# PLL.net
KiCad netlist of a schematic drawn in Altium Designer
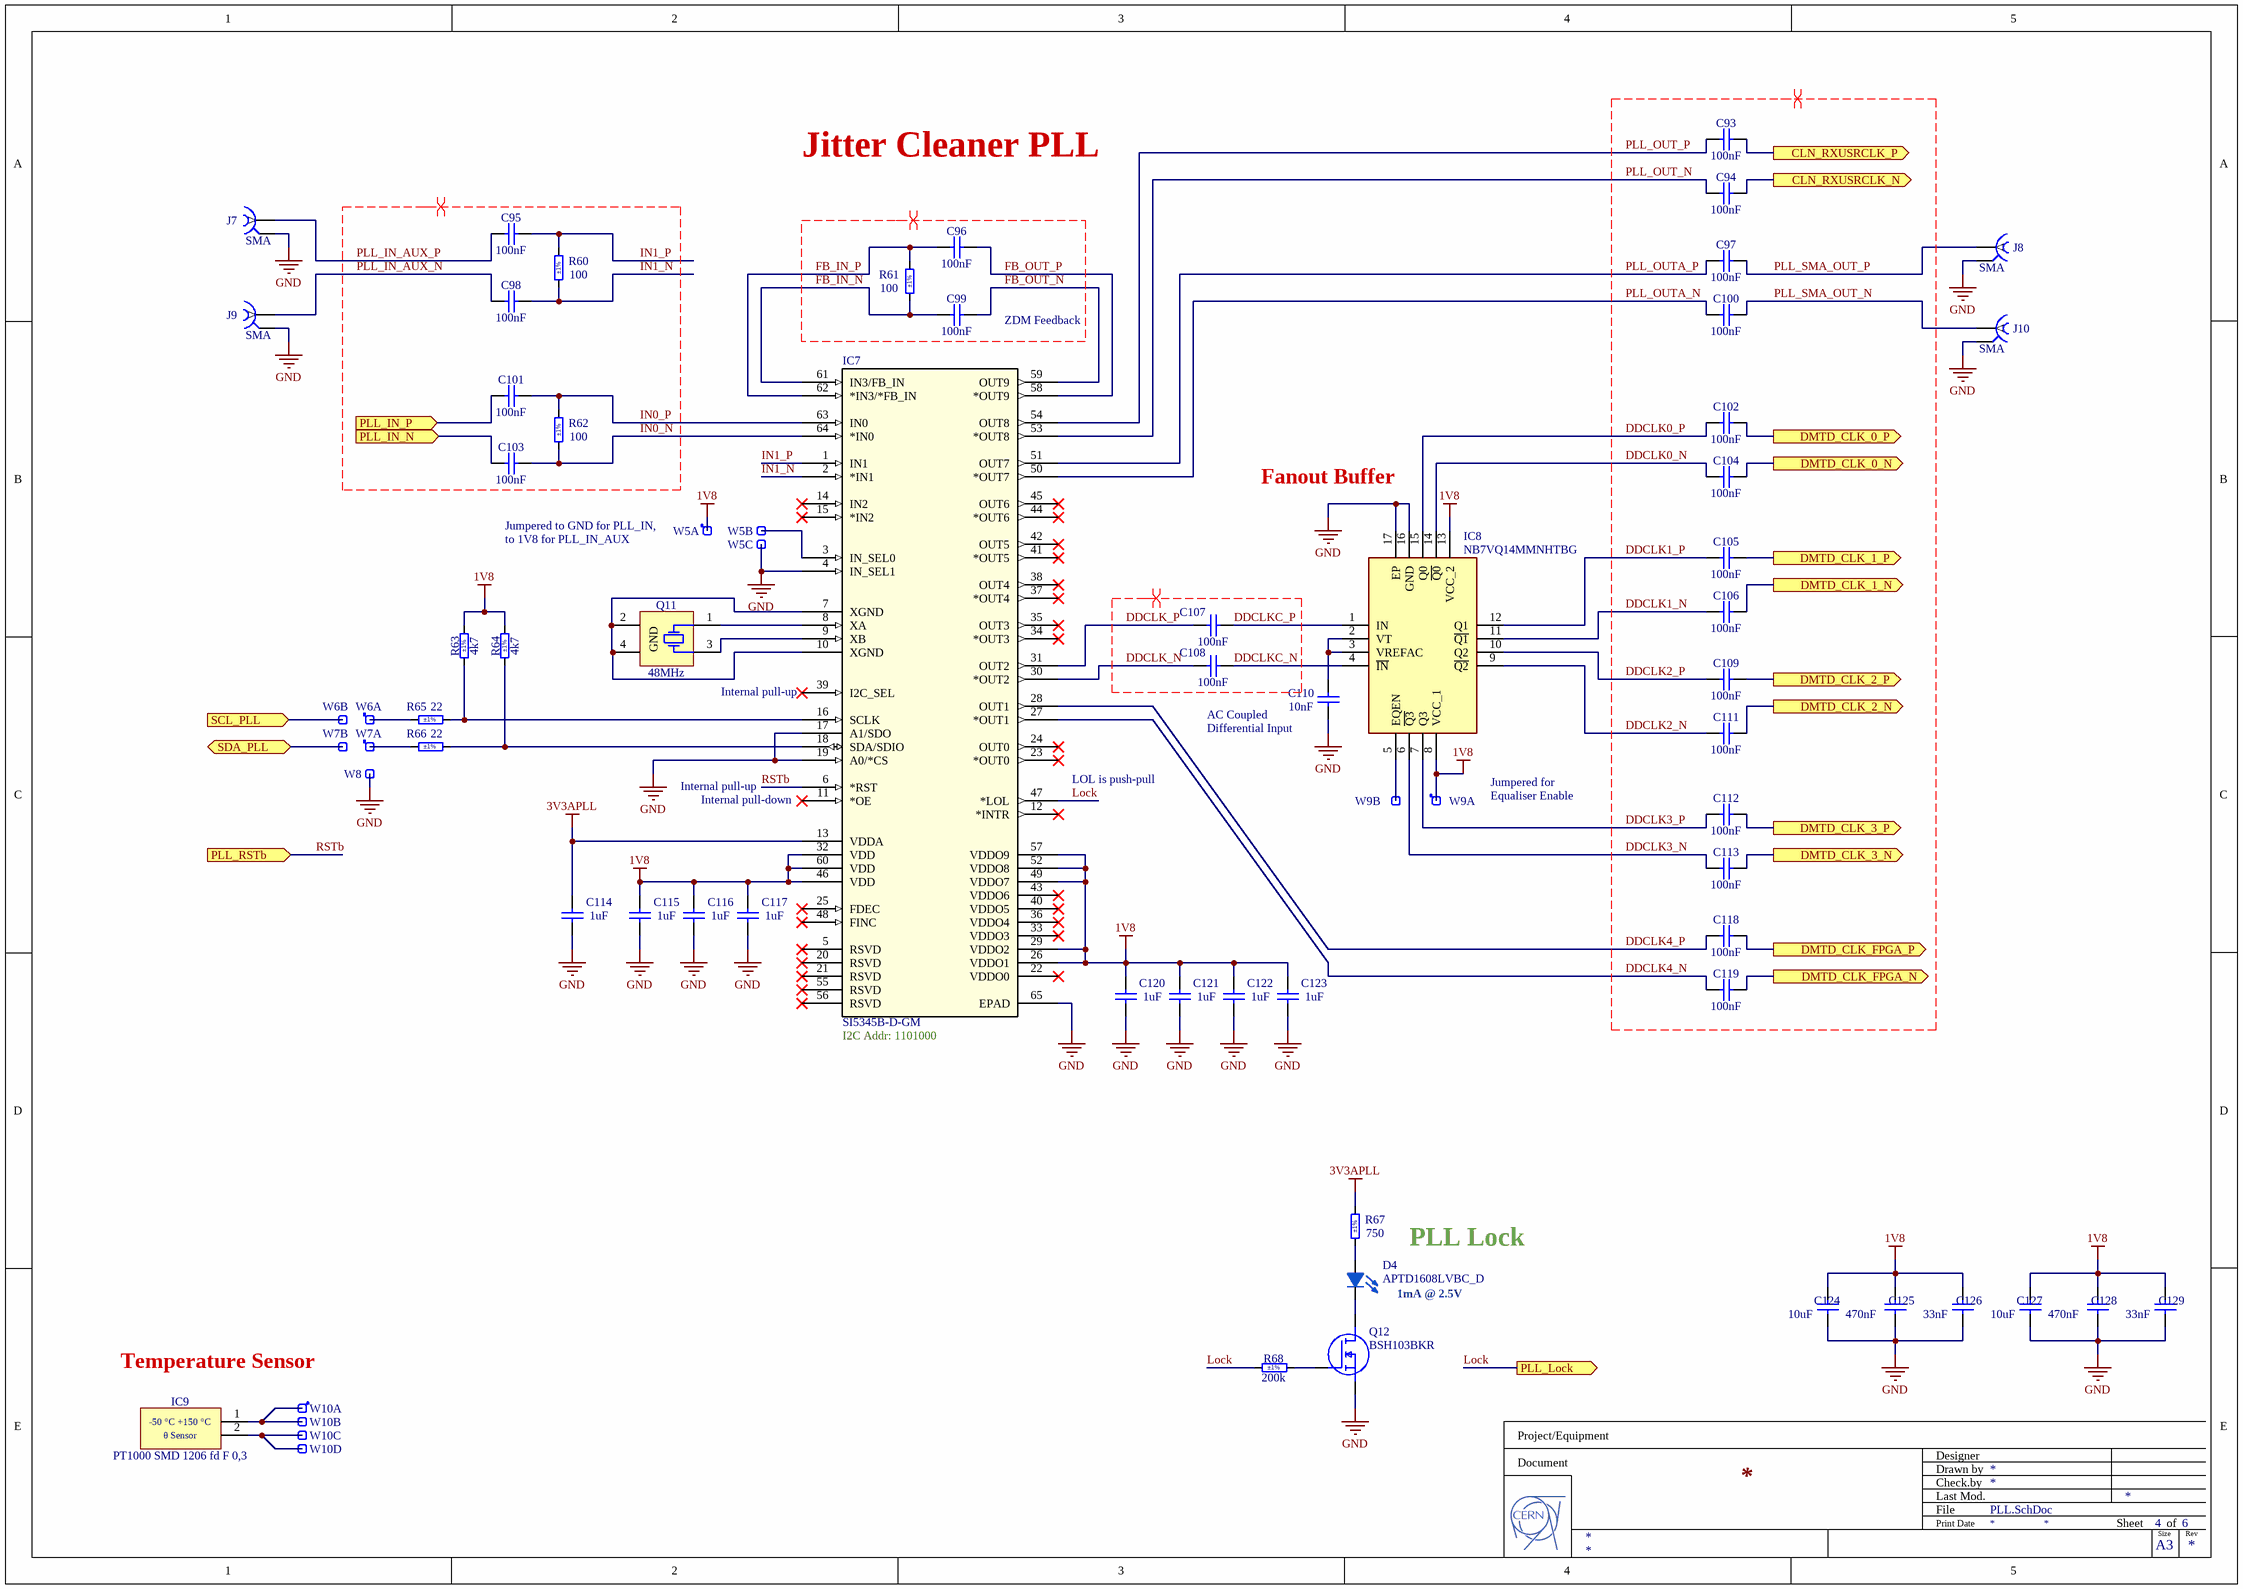
[diagram p0: PLL.SchDoc]

(export (version "E")
  (design (tool "Eeschema 10.0.6"))
  (components
    (comp (ref "C93")
      (value "100nF")
      (footprint "CAPC0603X33N")
      (description "Non-polarised capacitor")
      (fields
        (field (name "PART NUMBER") "CC0201_100NF_6.3V_10%_X7R")
        (field (name "VOLTAGE") "6.3V")
        (field (name "AUTHOR") "CERN DEM BC")
      )
      (libsource (lib "Capacitors") (part "Capacitor - non polarized"))
    )
    (comp (ref "C94")
      (value "100nF")
      (footprint "CAPC0603X33N")
      (description "Non-polarised capacitor")
      (fields
        (field (name "PART NUMBER") "CC0201_100NF_6.3V_10%_X7R")
        (field (name "VOLTAGE") "6.3V")
        (field (name "AUTHOR") "CERN DEM BC")
      )
      (libsource (lib "Capacitors") (part "Capacitor - non polarized"))
    )
    (comp (ref "C95")
      (value "100nF")
      (footprint "CAPC0603X33N")
      (description "Non-polarised capacitor")
      (fields
        (field (name "PART NUMBER") "CC0201_100NF_6.3V_10%_X7R")
        (field (name "VOLTAGE") "6.3V")
        (field (name "AUTHOR") "CERN DEM BC")
      )
      (libsource (lib "Capacitors") (part "Capacitor - non polarized"))
    )
    (comp (ref "C96")
      (value "100nF")
      (footprint "CAPC0603X33N")
      (description "Non-polarised capacitor")
      (fields
        (field (name "PART NUMBER") "CC0201_100NF_6.3V_10%_X7R")
        (field (name "VOLTAGE") "6.3V")
        (field (name "AUTHOR") "CERN DEM BC")
      )
      (libsource (lib "Capacitors") (part "Capacitor - non polarized"))
    )
    (comp (ref "C97")
      (value "100nF")
      (footprint "CAPC0603X33N")
      (description "Non-polarised capacitor")
      (fields
        (field (name "PART NUMBER") "CC0201_100NF_6.3V_10%_X7R")
        (field (name "VOLTAGE") "6.3V")
        (field (name "AUTHOR") "CERN DEM BC")
      )
      (libsource (lib "Capacitors") (part "Capacitor - non polarized"))
    )
    (comp (ref "C98")
      (value "100nF")
      (footprint "CAPC0603X33N")
      (description "Non-polarised capacitor")
      (fields
        (field (name "PART NUMBER") "CC0201_100NF_6.3V_10%_X7R")
        (field (name "VOLTAGE") "6.3V")
        (field (name "AUTHOR") "CERN DEM BC")
      )
      (libsource (lib "Capacitors") (part "Capacitor - non polarized"))
    )
    (comp (ref "C99")
      (value "100nF")
      (footprint "CAPC0603X33N")
      (description "Non-polarised capacitor")
      (fields
        (field (name "PART NUMBER") "CC0201_100NF_6.3V_10%_X7R")
        (field (name "VOLTAGE") "6.3V")
        (field (name "AUTHOR") "CERN DEM BC")
      )
      (libsource (lib "Capacitors") (part "Capacitor - non polarized"))
    )
    (comp (ref "C100")
      (value "100nF")
      (footprint "CAPC0603X33N")
      (description "Non-polarised capacitor")
      (fields
        (field (name "PART NUMBER") "CC0201_100NF_6.3V_10%_X7R")
        (field (name "VOLTAGE") "6.3V")
        (field (name "AUTHOR") "CERN DEM BC")
      )
      (libsource (lib "Capacitors") (part "Capacitor - non polarized"))
    )
    (comp (ref "C101")
      (value "100nF")
      (footprint "CAPC0603X33N")
      (description "Non-polarised capacitor")
      (fields
        (field (name "PART NUMBER") "CC0201_100NF_6.3V_10%_X7R")
        (field (name "VOLTAGE") "6.3V")
        (field (name "AUTHOR") "CERN DEM BC")
      )
      (libsource (lib "Capacitors") (part "Capacitor - non polarized"))
    )
    (comp (ref "C102")
      (value "100nF")
      (footprint "CAPC0603X33N")
      (description "Non-polarised capacitor")
      (fields
        (field (name "PART NUMBER") "CC0201_100NF_6.3V_10%_X7R")
        (field (name "VOLTAGE") "6.3V")
        (field (name "AUTHOR") "CERN DEM BC")
      )
      (libsource (lib "Capacitors") (part "Capacitor - non polarized"))
    )
    (comp (ref "C103")
      (value "100nF")
      (footprint "CAPC0603X33N")
      (description "Non-polarised capacitor")
      (fields
        (field (name "PART NUMBER") "CC0201_100NF_6.3V_10%_X7R")
        (field (name "VOLTAGE") "6.3V")
        (field (name "AUTHOR") "CERN DEM BC")
      )
      (libsource (lib "Capacitors") (part "Capacitor - non polarized"))
    )
    (comp (ref "C104")
      (value "100nF")
      (footprint "CAPC0603X33N")
      (description "Non-polarised capacitor")
      (fields
        (field (name "PART NUMBER") "CC0201_100NF_6.3V_10%_X7R")
        (field (name "VOLTAGE") "6.3V")
        (field (name "AUTHOR") "CERN DEM BC")
      )
      (libsource (lib "Capacitors") (part "Capacitor - non polarized"))
    )
    (comp (ref "C105")
      (value "100nF")
      (footprint "CAPC0603X33N")
      (description "Non-polarised capacitor")
      (fields
        (field (name "PART NUMBER") "CC0201_100NF_6.3V_10%_X7R")
        (field (name "VOLTAGE") "6.3V")
        (field (name "AUTHOR") "CERN DEM BC")
      )
      (libsource (lib "Capacitors") (part "Capacitor - non polarized"))
    )
    (comp (ref "C106")
      (value "100nF")
      (footprint "CAPC0603X33N")
      (description "Non-polarised capacitor")
      (fields
        (field (name "PART NUMBER") "CC0201_100NF_6.3V_10%_X7R")
        (field (name "VOLTAGE") "6.3V")
        (field (name "AUTHOR") "CERN DEM BC")
      )
      (libsource (lib "Capacitors") (part "Capacitor - non polarized"))
    )
    (comp (ref "C107")
      (value "100nF")
      (footprint "CAPC0603X33N")
      (description "Non-polarised capacitor")
      (fields
        (field (name "PART NUMBER") "CC0201_100NF_6.3V_10%_X7R")
        (field (name "VOLTAGE") "6.3V")
        (field (name "AUTHOR") "CERN DEM BC")
      )
      (libsource (lib "Capacitors") (part "Capacitor - non polarized"))
    )
    (comp (ref "C108")
      (value "100nF")
      (footprint "CAPC0603X33N")
      (description "Non-polarised capacitor")
      (fields
        (field (name "PART NUMBER") "CC0201_100NF_6.3V_10%_X7R")
        (field (name "VOLTAGE") "6.3V")
        (field (name "AUTHOR") "CERN DEM BC")
      )
      (libsource (lib "Capacitors") (part "Capacitor - non polarized"))
    )
    (comp (ref "C109")
      (value "100nF")
      (footprint "CAPC0603X33N")
      (description "Non-polarised capacitor")
      (fields
        (field (name "PART NUMBER") "CC0201_100NF_6.3V_10%_X7R")
        (field (name "VOLTAGE") "6.3V")
        (field (name "AUTHOR") "CERN DEM BC")
      )
      (libsource (lib "Capacitors") (part "Capacitor - non polarized"))
    )
    (comp (ref "C110")
      (value "10nF")
      (footprint "CAPC0603X33N")
      (description "Non-polarised capacitor")
      (fields
        (field (name "PART NUMBER") "CC0201_10NF_10V_10%_X5R")
        (field (name "VOLTAGE") "10V")
        (field (name "AUTHOR") "CERN DEM JLC")
      )
      (libsource (lib "Capacitors") (part "Capacitor - non polarized"))
    )
    (comp (ref "C111")
      (value "100nF")
      (footprint "CAPC0603X33N")
      (description "Non-polarised capacitor")
      (fields
        (field (name "PART NUMBER") "CC0201_100NF_6.3V_10%_X7R")
        (field (name "VOLTAGE") "6.3V")
        (field (name "AUTHOR") "CERN DEM BC")
      )
      (libsource (lib "Capacitors") (part "Capacitor - non polarized"))
    )
    (comp (ref "C112")
      (value "100nF")
      (footprint "CAPC0603X33N")
      (description "Non-polarised capacitor")
      (fields
        (field (name "PART NUMBER") "CC0201_100NF_6.3V_10%_X7R")
        (field (name "VOLTAGE") "6.3V")
        (field (name "AUTHOR") "CERN DEM BC")
      )
      (libsource (lib "Capacitors") (part "Capacitor - non polarized"))
    )
    (comp (ref "C113")
      (value "100nF")
      (footprint "CAPC0603X33N")
      (description "Non-polarised capacitor")
      (fields
        (field (name "PART NUMBER") "CC0201_100NF_6.3V_10%_X7R")
        (field (name "VOLTAGE") "6.3V")
        (field (name "AUTHOR") "CERN DEM BC")
      )
      (libsource (lib "Capacitors") (part "Capacitor - non polarized"))
    )
    (comp (ref "C114")
      (value "1uF")
      (footprint "CAPC1005X55N")
      (description "GRM153B30J105ME15")
      (fields
        (field (name "PART NUMBER") "CC0402_1UF_16V_10%_X5R")
        (field (name "VOLTAGE") "16V")
        (field (name "AUTHOR") "CERN DEM JLC")
      )
      (libsource (lib "Capacitors") (part "Capacitor - non polarized"))
    )
    (comp (ref "C115")
      (value "1uF")
      (footprint "CAPC1005X55N")
      (description "GRM153B30J105ME15")
      (fields
        (field (name "PART NUMBER") "CC0402_1UF_16V_10%_X5R")
        (field (name "VOLTAGE") "16V")
        (field (name "AUTHOR") "CERN DEM JLC")
      )
      (libsource (lib "Capacitors") (part "Capacitor - non polarized"))
    )
    (comp (ref "C116")
      (value "1uF")
      (footprint "CAPC1005X55N")
      (description "GRM153B30J105ME15")
      (fields
        (field (name "PART NUMBER") "CC0402_1UF_16V_10%_X5R")
        (field (name "VOLTAGE") "16V")
        (field (name "AUTHOR") "CERN DEM JLC")
      )
      (libsource (lib "Capacitors") (part "Capacitor - non polarized"))
    )
    (comp (ref "C117")
      (value "1uF")
      (footprint "CAPC1005X55N")
      (description "GRM153B30J105ME15")
      (fields
        (field (name "PART NUMBER") "CC0402_1UF_16V_10%_X5R")
        (field (name "VOLTAGE") "16V")
        (field (name "AUTHOR") "CERN DEM JLC")
      )
      (libsource (lib "Capacitors") (part "Capacitor - non polarized"))
    )
    (comp (ref "C118")
      (value "100nF")
      (footprint "CAPC0603X33N")
      (description "Non-polarised capacitor")
      (fields
        (field (name "PART NUMBER") "CC0201_100NF_6.3V_10%_X7R")
        (field (name "VOLTAGE") "6.3V")
        (field (name "AUTHOR") "CERN DEM BC")
      )
      (libsource (lib "Capacitors") (part "Capacitor - non polarized"))
    )
    (comp (ref "C119")
      (value "100nF")
      (footprint "CAPC0603X33N")
      (description "Non-polarised capacitor")
      (fields
        (field (name "PART NUMBER") "CC0201_100NF_6.3V_10%_X7R")
        (field (name "VOLTAGE") "6.3V")
        (field (name "AUTHOR") "CERN DEM BC")
      )
      (libsource (lib "Capacitors") (part "Capacitor - non polarized"))
    )
    (comp (ref "C120")
      (value "1uF")
      (footprint "CAPC1005X55N")
      (description "GRM153B30J105ME15")
      (fields
        (field (name "PART NUMBER") "CC0402_1UF_16V_10%_X5R")
        (field (name "VOLTAGE") "16V")
        (field (name "AUTHOR") "CERN DEM JLC")
      )
      (libsource (lib "Capacitors") (part "Capacitor - non polarized"))
    )
    (comp (ref "C121")
      (value "1uF")
      (footprint "CAPC1005X55N")
      (description "GRM153B30J105ME15")
      (fields
        (field (name "PART NUMBER") "CC0402_1UF_16V_10%_X5R")
        (field (name "VOLTAGE") "16V")
        (field (name "AUTHOR") "CERN DEM JLC")
      )
      (libsource (lib "Capacitors") (part "Capacitor - non polarized"))
    )
    (comp (ref "C122")
      (value "1uF")
      (footprint "CAPC1005X55N")
      (description "GRM153B30J105ME15")
      (fields
        (field (name "PART NUMBER") "CC0402_1UF_16V_10%_X5R")
        (field (name "VOLTAGE") "16V")
        (field (name "AUTHOR") "CERN DEM JLC")
      )
      (libsource (lib "Capacitors") (part "Capacitor - non polarized"))
    )
    (comp (ref "C123")
      (value "1uF")
      (footprint "CAPC1005X55N")
      (description "GRM153B30J105ME15")
      (fields
        (field (name "PART NUMBER") "CC0402_1UF_16V_10%_X5R")
        (field (name "VOLTAGE") "16V")
        (field (name "AUTHOR") "CERN DEM JLC")
      )
      (libsource (lib "Capacitors") (part "Capacitor - non polarized"))
    )
    (comp (ref "C124")
      (value "10uF")
      (footprint "CAPC1608X87N")
      (description "GRM188D71A106KA73")
      (fields
        (field (name "PART NUMBER") "CC0603_10UF_6.3V_20%_X5R")
        (field (name "VOLTAGE") "6.3V")
        (field (name "AUTHOR") "CERN DEM JLC")
      )
      (libsource (lib "Capacitors") (part "Capacitor - non polarized"))
    )
    (comp (ref "C125")
      (value "470nF")
      (footprint "CAPC0510X04N")
      (description "LLL153C70G474ME17")
      (libsource (lib "auxiliary_library") (part "Capacitor - non polarized"))
    )
    (comp (ref "C126")
      (value "33nF")
      (footprint "LLL03TR61E333KE01")
      (description "LLL03TR61E333KE01")
      (libsource (lib "auxiliary_library") (part "Capacitor - non polarized"))
    )
    (comp (ref "C127")
      (value "10uF")
      (footprint "CAPC1608X87N")
      (description "GRM188D71A106KA73")
      (fields
        (field (name "PART NUMBER") "CC0603_10UF_6.3V_20%_X5R")
        (field (name "VOLTAGE") "6.3V")
        (field (name "AUTHOR") "CERN DEM JLC")
      )
      (libsource (lib "Capacitors") (part "Capacitor - non polarized"))
    )
    (comp (ref "C128")
      (value "470nF")
      (footprint "CAPC0510X04N")
      (description "LLL153C70G474ME17")
      (libsource (lib "auxiliary_library") (part "Capacitor - non polarized"))
    )
    (comp (ref "C129")
      (value "33nF")
      (footprint "LLL03TR61E333KE01")
      (description "LLL03TR61E333KE01")
      (libsource (lib "auxiliary_library") (part "Capacitor - non polarized"))
    )
    (comp (ref "D4")
      (value "APTD1608LVBC_D")
      (footprint "LEDC1608X110N:LEDC1608X110N")
      (description "Led Blue 0603 2mA 2.65V 65mcd 120mW")
      (fields
        (field (name "MOUSER PART NUMBER") "604-APTD1608LVBCD")
        (field (name "MANUFACTURER_PART_NUMBER") "APTD1608LVBC/D")
      )
      (libsource (lib "APTD1608LVBC_D") (part "APTD1608LVBC_D"))
    )
    (comp (ref "IC7")
      (value "SI5345B-D-GM")
      (footprint "SamacSys:QFN50P900X900X90-65N-D")
      (description "Integrated Circuit")
      (fields (field (name "MOUSER PART NUMBER") "634-SI5345B-D-GM"))
      (libsource (lib "SamacSys") (part "SI5345B-D-GM"))
    )
    (comp (ref "IC8")
      (value "NB7VQ14MMNHTBG")
      (footprint "SamacSys:QFN50P300X300X100-17N")
      (description "Integrated Circuit")
      (fields (field (name "MOUSER PART NUMBER") "863-NB7VQ14MMNHTBG"))
      (libsource (lib "*") (part "NB7VQ14MMNHTBG"))
    )
    (comp (ref "IC9")
      (value "PT1000 SMD 1206 fd F 0,3")
      (footprint "DFN310X150X55-2N")
      (description "2 Pin Temperature Sensor")
      (fields
        (field (name "MANUFACTURER") "UMWELTSENSORTECHNIK GmbH (UST)")
        (field (name "AUTHOR") "CERN DEM JLC")
      )
      (libsource (lib "ICs And Semiconductors") (part "2 Pin Temperature Sensor -50+150"))
    )
    (comp (ref "J7")
      (value "SMA")
      (footprint "SAMTEC_SMA-J-P-H-ST-MT1")
      (fields
        (field (name "PART NUMBER") "SAMTEC_SMA-J-P-H-ST-MT1")
        (field (name "MANUFACTURER") "SAMTEC")
        (field (name "MANUFACTURER PART NUMBER") "SMA-J-P-H-ST-MT1")
        (field (name "AUTHOR") "CERN DEM HF")
      )
      (libsource (lib "") (part "Coax_1Female_1Shield_1"))
    )
    (comp (ref "J8")
      (value "SMA")
      (footprint "SAMTEC_SMA-J-P-H-ST-MT1")
      (fields
        (field (name "PART NUMBER") "SAMTEC_SMA-J-P-H-ST-MT1")
        (field (name "MANUFACTURER") "SAMTEC")
        (field (name "MANUFACTURER PART NUMBER") "SMA-J-P-H-ST-MT1")
        (field (name "AUTHOR") "CERN DEM HF")
      )
      (libsource (lib "Connectors") (part "Coax_1Female_1Shield"))
    )
    (comp (ref "J9")
      (value "SMA")
      (footprint "SAMTEC_SMA-J-P-H-ST-MT1")
      (fields
        (field (name "PART NUMBER") "SAMTEC_SMA-J-P-H-ST-MT1")
        (field (name "MANUFACTURER") "SAMTEC")
        (field (name "MANUFACTURER PART NUMBER") "SMA-J-P-H-ST-MT1")
        (field (name "AUTHOR") "CERN DEM HF")
      )
      (libsource (lib "") (part "Coax_1Female_1Shield_1"))
    )
    (comp (ref "J10")
      (value "SMA")
      (footprint "SAMTEC_SMA-J-P-H-ST-MT1")
      (fields
        (field (name "PART NUMBER") "SAMTEC_SMA-J-P-H-ST-MT1")
        (field (name "MANUFACTURER") "SAMTEC")
        (field (name "MANUFACTURER PART NUMBER") "SMA-J-P-H-ST-MT1")
        (field (name "AUTHOR") "CERN DEM HF")
      )
      (libsource (lib "Connectors") (part "Coax_1Female_1Shield"))
    )
    (comp (ref "Q11")
      (value "48MHz")
      (footprint "XTAL_KYOCERA_CX3225SB")
      (description "Crystal 4 pins 1=XTAL Control 2=GND3=XTAL 4=GND")
      (fields
        (field (name "PART NUMBER") "XTAL_48MHZ_KYOCERA_CX3225SB48000D0FPJC1")
        (field (name "MANUFACTURER") "KYOCERA")
        (field (name "AUTHOR") "CERN DEM JLC")
      )
      (libsource (lib "ICs And Semiconductors") (part "Quartz Crystal 1X 2GND 3X 4GND"))
    )
    (comp (ref "Q12")
      (value "BSH103BKR")
      (footprint "SamacSys:SOT95P230X110-3N")
      (description "MOSFET (N-Channel)")
      (fields (field (name "MOUSER PART NUMBER") "771-BSH103BKR"))
      (libsource (lib "SamacSys") (part "BSH103BKR"))
    )
    (comp (ref "R60")
      (value "100")
      (footprint "RESC0603X28N")
      (description "Resistor - 1%")
      (fields
        (field (name "TOLERANCE") "±1%")
        (field (name "PART NUMBER") "R0201_100R_1%_0.05W_200PPM")
        (field (name "POWER") "0.05W")
        (field (name "AUTHOR") "CERN DEM JLC")
      )
      (libsource (lib "Resistors") (part "Resistor - 1%"))
    )
    (comp (ref "R61")
      (value "100")
      (footprint "RESC0603X28N")
      (description "Resistor - 1%")
      (fields
        (field (name "TOLERANCE") "±1%")
        (field (name "PART NUMBER") "R0201_100R_1%_0.05W_200PPM")
        (field (name "POWER") "0.05W")
        (field (name "AUTHOR") "CERN DEM JLC")
      )
      (libsource (lib "Resistors") (part "Resistor - 1%"))
    )
    (comp (ref "R62")
      (value "100")
      (footprint "RESC0603X28N")
      (description "Resistor - 1%")
      (fields
        (field (name "TOLERANCE") "±1%")
        (field (name "PART NUMBER") "R0201_100R_1%_0.05W_200PPM")
        (field (name "POWER") "0.05W")
        (field (name "AUTHOR") "CERN DEM JLC")
      )
      (libsource (lib "Resistors") (part "Resistor - 1%"))
    )
    (comp (ref "R63")
      (value "4k7")
      (footprint "RESC1005X40N")
      (description "Resistor - 1%")
      (fields
        (field (name "TOLERANCE") "±1%")
        (field (name "PART NUMBER") "R0402_4K7_1%_0.0625W_100PPM")
        (field (name "POWER") "0.0625W")
        (field (name "AUTHOR") "CERN DEM JLC")
      )
      (libsource (lib "Resistors") (part "Resistor - 1%"))
    )
    (comp (ref "R64")
      (value "4k7")
      (footprint "RESC1005X40N")
      (description "Resistor - 1%")
      (fields
        (field (name "TOLERANCE") "±1%")
        (field (name "PART NUMBER") "R0402_4K7_1%_0.0625W_100PPM")
        (field (name "POWER") "0.0625W")
        (field (name "AUTHOR") "CERN DEM JLC")
      )
      (libsource (lib "Resistors") (part "Resistor - 1%"))
    )
    (comp (ref "R65")
      (value "22")
      (footprint "RESC1005X40N")
      (description "Resistor - 1%")
      (fields
        (field (name "TOLERANCE") "±1%")
        (field (name "PART NUMBER") "R0402_22R_1%_0.0625W_100PPM")
        (field (name "POWER") "0.0625W")
        (field (name "AUTHOR") "CERN DEM JLC")
      )
      (libsource (lib "Resistors") (part "Resistor - 1%"))
    )
    (comp (ref "R66")
      (value "22")
      (footprint "RESC1005X40N")
      (description "Resistor - 1%")
      (fields
        (field (name "TOLERANCE") "±1%")
        (field (name "PART NUMBER") "R0402_22R_1%_0.0625W_100PPM")
        (field (name "POWER") "0.0625W")
        (field (name "AUTHOR") "CERN DEM JLC")
      )
      (libsource (lib "Resistors") (part "Resistor - 1%"))
    )
    (comp (ref "R67")
      (value "750")
      (footprint "RESC1005X40N")
      (description "Resistor - 1%")
      (fields
        (field (name "TOLERANCE") "±1%")
        (field (name "PART NUMBER") "R0402_750R_1%_0.0625W_100PPM")
        (field (name "POWER") "0.0625W")
        (field (name "AUTHOR") "CERN DEM JLC")
      )
      (libsource (lib "Resistors") (part "Resistor - 1%"))
    )
    (comp (ref "R68")
      (value "200k")
      (footprint "RESC1005X40N")
      (description "Resistor - 1%")
      (fields
        (field (name "TOLERANCE") "±1%")
        (field (name "PART NUMBER") "R0402_200K_1%_0.0625W_100PPM")
        (field (name "POWER") "0.0625W")
        (field (name "AUTHOR") "CERN DEM JLC")
      )
      (libsource (lib "Resistors") (part "Resistor - 1%"))
    )
    (comp (ref "W5")
      (value "Header 3")
      (footprint "SAMTEC_HTSW-103-23-L-S")
      (description "3 Mini Wire-Wrap Contact Strip Header")
      (fields
        (field (name "PART NUMBER") "SAMTEC_HTSW-103-23-L-S")
        (field (name "MANUFACTURER") "SAMTEC")
        (field (name "AUTHOR") "CERN DEM JLC")
      )
      (libsource (lib "Connectors") (part "Wire-Wrap Contact x3"))
    )
    (comp (ref "W6")
      (value "Header 2")
      (footprint "SAMTEC_HTSW-102-23-L-S")
      (description "2 Mini Wire-Wrap Contact Strip Header")
      (fields
        (field (name "PART NUMBER") "SAMTEC_HTSW-102-23-L-S")
        (field (name "MANUFACTURER") "SAMTEC")
        (field (name "AUTHOR") "CERN DEM JLC")
      )
      (libsource (lib "Connectors") (part "Wire-Wrap Contact x2"))
    )
    (comp (ref "W7")
      (value "Header 2")
      (footprint "SAMTEC_HTSW-102-23-L-S")
      (description "2 Mini Wire-Wrap Contact Strip Header")
      (fields
        (field (name "PART NUMBER") "SAMTEC_HTSW-102-23-L-S")
        (field (name "MANUFACTURER") "SAMTEC")
        (field (name "AUTHOR") "CERN DEM JLC")
      )
      (libsource (lib "Connectors") (part "Wire-Wrap Contact x2"))
    )
    (comp (ref "W8")
      (value "Header 1")
      (footprint "SAMTEC_HTSW-101-23-L-S")
      (description "Single Mini Wire-Wrap Contact")
      (fields
        (field (name "PART NUMBER") "SAMTEC_HTSW-101-23-L-S")
        (field (name "MANUFACTURER") "SAMTEC")
        (field (name "AUTHOR") "CERN DEM JLC")
      )
      (libsource (lib "Connectors") (part "Wire-Wrap Contact"))
    )
    (comp (ref "W9")
      (value "Header 2")
      (footprint "SAMTEC_HTSW-102-23-L-S")
      (description "2 Mini Wire-Wrap Contact Strip Header")
      (fields
        (field (name "PART NUMBER") "SAMTEC_HTSW-102-23-L-S")
        (field (name "MANUFACTURER") "SAMTEC")
        (field (name "AUTHOR") "CERN DEM JLC")
      )
      (libsource (lib "Connectors") (part "Wire-Wrap Contact x2"))
    )
    (comp (ref "W10")
      (value "Header 4")
      (footprint "SAMTEC_HTSW-104-23-L-S")
      (description "4 Mini Wire-Wrap Contact Strip Header")
      (fields
        (field (name "PART NUMBER") "SAMTEC_HTSW-104-23-L-S")
        (field (name "MANUFACTURER") "SAMTEC")
        (field (name "AUTHOR") "CERN DEM JLC")
      )
      (libsource (lib "Connectors") (part "Wire-Wrap Contact x4"))
    )
  )
  (nets
    (net (code "1") (name "/CLN_RXUSRCLK_N") (class "Default")
      (node (ref "C94") (pin "2") (pinfunction "2_2") (pintype "passive"))
    )
    (net (code "2") (name "/CLN_RXUSRCLK_P") (class "Default")
      (node (ref "C93") (pin "2") (pinfunction "2_2") (pintype "passive"))
    )
    (net (code "3") (name "/DDCLK0_N") (class "Default")
      (node (ref "C104") (pin "1") (pinfunction "1_1") (pintype "passive"))
      (node (ref "IC8") (pin "14") (pinfunction "~{Q0}_14") (pintype "passive"))
    )
    (net (code "4") (name "/DDCLK0_P") (class "Default")
      (node (ref "C102") (pin "1") (pinfunction "1_1") (pintype "passive"))
      (node (ref "IC8") (pin "15") (pinfunction "Q0_15") (pintype "passive"))
    )
    (net (code "5") (name "/DDCLK1_N") (class "Default")
      (node (ref "C106") (pin "1") (pinfunction "1_1") (pintype "passive"))
      (node (ref "IC8") (pin "11") (pinfunction "~{Q1}_11") (pintype "passive"))
    )
    (net (code "6") (name "/DDCLK1_P") (class "Default")
      (node (ref "C105") (pin "1") (pinfunction "1_1") (pintype "passive"))
      (node (ref "IC8") (pin "12") (pinfunction "Q1_12") (pintype "passive"))
    )
    (net (code "7") (name "/DDCLK2_N") (class "Default")
      (node (ref "C111") (pin "1") (pinfunction "1_1") (pintype "passive"))
      (node (ref "IC8") (pin "9") (pinfunction "~{Q2}_9") (pintype "passive"))
    )
    (net (code "8") (name "/DDCLK2_P") (class "Default")
      (node (ref "C109") (pin "1") (pinfunction "1_1") (pintype "passive"))
      (node (ref "IC8") (pin "10") (pinfunction "Q2_10") (pintype "passive"))
    )
    (net (code "9") (name "/DDCLK3_N") (class "Default")
      (node (ref "C113") (pin "1") (pinfunction "1_1") (pintype "passive"))
      (node (ref "IC8") (pin "6") (pinfunction "~{Q3}_6") (pintype "passive"))
    )
    (net (code "10") (name "/DDCLK3_P") (class "Default")
      (node (ref "C112") (pin "1") (pinfunction "1_1") (pintype "passive"))
      (node (ref "IC8") (pin "7") (pinfunction "Q3_7") (pintype "passive"))
    )
    (net (code "11") (name "/DDCLK4_N") (class "Default")
      (node (ref "C119") (pin "1") (pinfunction "1_1") (pintype "passive"))
      (node (ref "IC7") (pin "27") (pinfunction "*OUT1_27") (pintype "output"))
    )
    (net (code "12") (name "/DDCLK4_P") (class "Default")
      (node (ref "C118") (pin "1") (pinfunction "1_1") (pintype "passive"))
      (node (ref "IC7") (pin "28") (pinfunction "OUT1_28") (pintype "output"))
    )
    (net (code "13") (name "/DDCLKC_N") (class "Default")
      (node (ref "C108") (pin "2") (pinfunction "2_2") (pintype "passive"))
      (node (ref "IC8") (pin "4") (pinfunction "~{IN}_4") (pintype "passive"))
    )
    (net (code "14") (name "/DDCLKC_P") (class "Default")
      (node (ref "C107") (pin "2") (pinfunction "2_2") (pintype "passive"))
      (node (ref "IC8") (pin "1") (pinfunction "IN_1") (pintype "passive"))
    )
    (net (code "15") (name "/DDCLK_N") (class "Default")
      (node (ref "C108") (pin "1") (pinfunction "1_1") (pintype "passive"))
      (node (ref "IC7") (pin "30") (pinfunction "*OUT2_30") (pintype "output"))
    )
    (net (code "16") (name "/DDCLK_P") (class "Default")
      (node (ref "C107") (pin "1") (pinfunction "1_1") (pintype "passive"))
      (node (ref "IC7") (pin "31") (pinfunction "OUT2_31") (pintype "output"))
    )
    (net (code "17") (name "/DMTD_CLK_0_N") (class "Default")
      (node (ref "C104") (pin "2") (pinfunction "2_2") (pintype "passive"))
    )
    (net (code "18") (name "/DMTD_CLK_0_P") (class "Default")
      (node (ref "C102") (pin "2") (pinfunction "2_2") (pintype "passive"))
    )
    (net (code "19") (name "/DMTD_CLK_1_N") (class "Default")
      (node (ref "C106") (pin "2") (pinfunction "2_2") (pintype "passive"))
    )
    (net (code "20") (name "/DMTD_CLK_1_P") (class "Default")
      (node (ref "C105") (pin "2") (pinfunction "2_2") (pintype "passive"))
    )
    (net (code "21") (name "/DMTD_CLK_2_N") (class "Default")
      (node (ref "C111") (pin "2") (pinfunction "2_2") (pintype "passive"))
    )
    (net (code "22") (name "/DMTD_CLK_2_P") (class "Default")
      (node (ref "C109") (pin "2") (pinfunction "2_2") (pintype "passive"))
    )
    (net (code "23") (name "/DMTD_CLK_3_N") (class "Default")
      (node (ref "C113") (pin "2") (pinfunction "2_2") (pintype "passive"))
    )
    (net (code "24") (name "/DMTD_CLK_3_P") (class "Default")
      (node (ref "C112") (pin "2") (pinfunction "2_2") (pintype "passive"))
    )
    (net (code "25") (name "/DMTD_CLK_FPGA_N") (class "Default")
      (node (ref "C119") (pin "2") (pinfunction "2_2") (pintype "passive"))
    )
    (net (code "26") (name "/DMTD_CLK_FPGA_P") (class "Default")
      (node (ref "C118") (pin "2") (pinfunction "2_2") (pintype "passive"))
    )
    (net (code "27") (name "/FB_IN_N") (class "Default")
      (node (ref "C99") (pin "1") (pinfunction "1_1") (pintype "passive"))
      (node (ref "IC7") (pin "61") (pinfunction "IN3/FB_IN_61") (pintype "input"))
      (node (ref "R61") (pin "1") (pinfunction "1_1") (pintype "passive"))
    )
    (net (code "28") (name "/FB_IN_P") (class "Default")
      (node (ref "C96") (pin "1") (pinfunction "1_1") (pintype "passive"))
      (node (ref "IC7") (pin "62") (pinfunction "*IN3/*FB_IN_62") (pintype "input"))
      (node (ref "R61") (pin "2") (pinfunction "2_2") (pintype "passive"))
    )
    (net (code "29") (name "/FB_OUT_N") (class "Default")
      (node (ref "C99") (pin "2") (pinfunction "2_2") (pintype "passive"))
      (node (ref "IC7") (pin "59") (pinfunction "OUT9_59") (pintype "output"))
    )
    (net (code "30") (name "/FB_OUT_P") (class "Default")
      (node (ref "C96") (pin "2") (pinfunction "2_2") (pintype "passive"))
      (node (ref "IC7") (pin "58") (pinfunction "*OUT9_58") (pintype "output"))
    )
    (net (code "31") (name "/IN0_N") (class "Default")
      (node (ref "C103") (pin "1") (pinfunction "1_1") (pintype "passive"))
      (node (ref "IC7") (pin "64") (pinfunction "*IN0_64") (pintype "input"))
      (node (ref "R62") (pin "1") (pinfunction "1_1") (pintype "passive"))
    )
    (net (code "32") (name "/IN0_P") (class "Default")
      (node (ref "C101") (pin "1") (pinfunction "1_1") (pintype "passive"))
      (node (ref "IC7") (pin "63") (pinfunction "IN0_63") (pintype "input"))
      (node (ref "R62") (pin "2") (pinfunction "2_2") (pintype "passive"))
    )
    (net (code "33") (name "/IN1_N") (class "Default")
      (node (ref "C98") (pin "1") (pinfunction "1_1") (pintype "passive"))
      (node (ref "IC7") (pin "2") (pinfunction "*IN1_2") (pintype "input"))
      (node (ref "R60") (pin "1") (pinfunction "1_1") (pintype "passive"))
    )
    (net (code "34") (name "/IN1_P") (class "Default")
      (node (ref "C95") (pin "1") (pinfunction "1_1") (pintype "passive"))
      (node (ref "IC7") (pin "1") (pinfunction "IN1_1") (pintype "input"))
      (node (ref "R60") (pin "2") (pinfunction "2_2") (pintype "passive"))
    )
    (net (code "35") (name "/Lock") (class "Default")
      (node (ref "IC7") (pin "47") (pinfunction "*LOL_47") (pintype "output"))
      (node (ref "R68") (pin "1") (pinfunction "1_1") (pintype "passive"))
    )
    (net (code "36") (name "/PLL_IN_AUX_N") (class "Default")
      (node (ref "C98") (pin "2") (pinfunction "2_2") (pintype "passive"))
      (node (ref "J9") (pin "1") (pinfunction "1_1") (pintype "output"))
    )
    (net (code "37") (name "/PLL_IN_AUX_P") (class "Default")
      (node (ref "C95") (pin "2") (pinfunction "2_2") (pintype "passive"))
      (node (ref "J7") (pin "1") (pinfunction "1_1") (pintype "output"))
    )
    (net (code "38") (name "/PLL_IN_N") (class "Default")
      (node (ref "C103") (pin "2") (pinfunction "2_2") (pintype "passive"))
    )
    (net (code "39") (name "/PLL_IN_P") (class "Default")
      (node (ref "C101") (pin "2") (pinfunction "2_2") (pintype "passive"))
    )
    (net (code "40") (name "/PLL_OUTA_N") (class "Default")
      (node (ref "C100") (pin "1") (pinfunction "1_1") (pintype "passive"))
      (node (ref "IC7") (pin "50") (pinfunction "*OUT7_50") (pintype "output"))
    )
    (net (code "41") (name "/PLL_OUTA_P") (class "Default")
      (node (ref "C97") (pin "1") (pinfunction "1_1") (pintype "passive"))
      (node (ref "IC7") (pin "51") (pinfunction "OUT7_51") (pintype "output"))
    )
    (net (code "42") (name "/PLL_OUT_N") (class "Default")
      (node (ref "C94") (pin "1") (pinfunction "1_1") (pintype "passive"))
      (node (ref "IC7") (pin "53") (pinfunction "*OUT8_53") (pintype "output"))
    )
    (net (code "43") (name "/PLL_OUT_P") (class "Default")
      (node (ref "C93") (pin "1") (pinfunction "1_1") (pintype "passive"))
      (node (ref "IC7") (pin "54") (pinfunction "OUT8_54") (pintype "output"))
    )
    (net (code "44") (name "/PLL_SMA_OUT_N") (class "Default")
      (node (ref "C100") (pin "2") (pinfunction "2_2") (pintype "passive"))
      (node (ref "J10") (pin "1") (pinfunction "1_1") (pintype "output"))
    )
    (net (code "45") (name "/PLL_SMA_OUT_P") (class "Default")
      (node (ref "C97") (pin "2") (pinfunction "2_2") (pintype "passive"))
      (node (ref "J8") (pin "1") (pinfunction "1_1") (pintype "output"))
    )
    (net (code "46") (name "/RSTb") (class "Default")
      (node (ref "IC7") (pin "6") (pinfunction "*RST_6") (pintype "input"))
    )
    (net (code "47") (name "/SCL_PLL") (class "Default")
      (node (ref "W6") (pin "2") (pinfunction "2_2") (pintype "passive"))
    )
    (net (code "48") (name "/SDA_PLL") (class "Default")
      (node (ref "W7") (pin "2") (pinfunction "2_2") (pintype "passive"))
    )
    (net (code "49") (name "1V8") (class "Default")
      (node (ref "C115") (pin "2") (pinfunction "2_2") (pintype "passive"))
      (node (ref "C116") (pin "2") (pinfunction "2_2") (pintype "passive"))
      (node (ref "C117") (pin "2") (pinfunction "2_2") (pintype "passive"))
      (node (ref "C120") (pin "2") (pinfunction "2_2") (pintype "passive"))
      (node (ref "C121") (pin "2") (pinfunction "2_2") (pintype "passive"))
      (node (ref "C122") (pin "2") (pinfunction "2_2") (pintype "passive"))
      (node (ref "C123") (pin "2") (pinfunction "2_2") (pintype "passive"))
      (node (ref "C124") (pin "2") (pinfunction "2_2") (pintype "passive"))
      (node (ref "C125") (pin "2") (pinfunction "2_2") (pintype "passive"))
      (node (ref "C126") (pin "2") (pinfunction "2_2") (pintype "passive"))
      (node (ref "C127") (pin "2") (pinfunction "2_2") (pintype "passive"))
      (node (ref "C128") (pin "2") (pinfunction "2_2") (pintype "passive"))
      (node (ref "C129") (pin "2") (pinfunction "2_2") (pintype "passive"))
      (node (ref "IC7") (pin "26") (pinfunction "VDDO1_26") (pintype "power_in"))
      (node (ref "IC7") (pin "29") (pinfunction "VDDO2_29") (pintype "power_in"))
      (node (ref "IC7") (pin "32") (pinfunction "VDD_32") (pintype "power_in"))
      (node (ref "IC7") (pin "46") (pinfunction "VDD_46") (pintype "power_in"))
      (node (ref "IC7") (pin "49") (pinfunction "VDDO7_49") (pintype "power_in"))
      (node (ref "IC7") (pin "52") (pinfunction "VDDO8_52") (pintype "power_in"))
      (node (ref "IC7") (pin "57") (pinfunction "VDDO9_57") (pintype "power_in"))
      (node (ref "IC7") (pin "60") (pinfunction "VDD_60") (pintype "power_in"))
      (node (ref "IC8") (pin "13") (pinfunction "VCC_2_13") (pintype "passive"))
      (node (ref "IC8") (pin "8") (pinfunction "VCC_1_8") (pintype "passive"))
      (node (ref "R63") (pin "2") (pinfunction "2_2") (pintype "passive"))
      (node (ref "R64") (pin "2") (pinfunction "2_2") (pintype "passive"))
      (node (ref "W5") (pin "1") (pinfunction "1_1") (pintype "passive"))
      (node (ref "W9") (pin "1") (pinfunction "1_1") (pintype "bidirectional"))
    )
    (net (code "50") (name "3V3APLL") (class "Default")
      (node (ref "C114") (pin "2") (pinfunction "2_2") (pintype "passive"))
      (node (ref "IC7") (pin "13") (pinfunction "VDDA_13") (pintype "power_in"))
      (node (ref "R67") (pin "2") (pinfunction "2_2") (pintype "passive"))
    )
    (net (code "51") (name "GND") (class "Default")
      (node (ref "C110") (pin "1") (pinfunction "1_1") (pintype "passive"))
      (node (ref "C114") (pin "1") (pinfunction "1_1") (pintype "passive"))
      (node (ref "C115") (pin "1") (pinfunction "1_1") (pintype "passive"))
      (node (ref "C116") (pin "1") (pinfunction "1_1") (pintype "passive"))
      (node (ref "C117") (pin "1") (pinfunction "1_1") (pintype "passive"))
      (node (ref "C120") (pin "1") (pinfunction "1_1") (pintype "passive"))
      (node (ref "C121") (pin "1") (pinfunction "1_1") (pintype "passive"))
      (node (ref "C122") (pin "1") (pinfunction "1_1") (pintype "passive"))
      (node (ref "C123") (pin "1") (pinfunction "1_1") (pintype "passive"))
      (node (ref "C124") (pin "1") (pinfunction "1_1") (pintype "passive"))
      (node (ref "C125") (pin "1") (pinfunction "1_1") (pintype "passive"))
      (node (ref "C126") (pin "1") (pinfunction "1_1") (pintype "passive"))
      (node (ref "C127") (pin "1") (pinfunction "1_1") (pintype "passive"))
      (node (ref "C128") (pin "1") (pinfunction "1_1") (pintype "passive"))
      (node (ref "C129") (pin "1") (pinfunction "1_1") (pintype "passive"))
      (node (ref "IC7") (pin "17") (pinfunction "A1/SDO_17") (pintype "passive"))
      (node (ref "IC7") (pin "19") (pinfunction "A0/*CS_19") (pintype "input"))
      (node (ref "IC7") (pin "4") (pinfunction "IN_SEL1_4") (pintype "input"))
      (node (ref "IC7") (pin "65") (pinfunction "EPAD_65") (pintype "passive"))
      (node (ref "IC8") (pin "16") (pinfunction "GND_16") (pintype "passive"))
      (node (ref "IC8") (pin "17") (pinfunction "EP_17") (pintype "passive"))
      (node (ref "J10") (pin "2") (pinfunction "2_2") (pintype "power_in"))
      (node (ref "J7") (pin "2") (pinfunction "2_2") (pintype "power_in"))
      (node (ref "J8") (pin "2") (pinfunction "2_2") (pintype "power_in"))
      (node (ref "J9") (pin "2") (pinfunction "2_2") (pintype "power_in"))
      (node (ref "Q12") (pin "2") (pinfunction "S_2") (pintype "passive"))
      (node (ref "W5") (pin "3") (pinfunction "3_3") (pintype "bidirectional"))
      (node (ref "W8") (pin "1") (pinfunction "1_1") (pintype "passive"))
    )
    (net (code "52") (name "Net-(D4-A)") (class "Default")
      (node (ref "D4") (pin "2") (pinfunction "A_2") (pintype "passive"))
      (node (ref "R67") (pin "1") (pinfunction "1_1") (pintype "passive"))
    )
    (net (code "53") (name "Net-(D4-C)") (class "Default")
      (node (ref "D4") (pin "1") (pinfunction "C_1") (pintype "passive"))
      (node (ref "Q12") (pin "3") (pinfunction "D_3") (pintype "passive"))
    )
    (net (code "54") (name "Net-(IC7-IN_SEL0)") (class "Default")
      (node (ref "IC7") (pin "3") (pinfunction "IN_SEL0_3") (pintype "input"))
      (node (ref "W5") (pin "2") (pinfunction "2_2") (pintype "bidirectional"))
    )
    (net (code "55") (name "Net-(IC7-SCLK)") (class "Default")
      (node (ref "IC7") (pin "16") (pinfunction "SCLK_16") (pintype "input"))
      (node (ref "R63") (pin "1") (pinfunction "1_1") (pintype "passive"))
      (node (ref "R65") (pin "2") (pinfunction "2_2") (pintype "passive"))
    )
    (net (code "56") (name "Net-(IC7-SDA{slash}SDIO)") (class "Default")
      (node (ref "IC7") (pin "18") (pinfunction "SDA/SDIO_18") (pintype "bidirectional"))
      (node (ref "R64") (pin "1") (pinfunction "1_1") (pintype "passive"))
      (node (ref "R66") (pin "2") (pinfunction "2_2") (pintype "passive"))
    )
    (net (code "57") (name "Net-(IC7-XA)") (class "Default")
      (node (ref "IC7") (pin "8") (pinfunction "XA_8") (pintype "input"))
      (node (ref "Q11") (pin "1") (pinfunction "X_1") (pintype "passive"))
    )
    (net (code "58") (name "Net-(IC7-XB)") (class "Default")
      (node (ref "IC7") (pin "9") (pinfunction "XB_9") (pintype "input"))
      (node (ref "Q11") (pin "3") (pinfunction "X_3") (pintype "passive"))
    )
    (net (code "59") (name "Net-(IC7-XGND-Pad10)") (class "Default")
      (node (ref "IC7") (pin "10") (pinfunction "XGND_10") (pintype "power_in"))
      (node (ref "IC7") (pin "7") (pinfunction "XGND_7") (pintype "power_in"))
      (node (ref "Q11") (pin "2") (pinfunction "GND_2") (pintype "power_in"))
      (node (ref "Q11") (pin "4") (pinfunction "GND_4") (pintype "power_in"))
    )
    (net (code "60") (name "Net-(IC8-EQEN)") (class "Default")
      (node (ref "IC8") (pin "5") (pinfunction "EQEN_5") (pintype "passive"))
      (node (ref "W9") (pin "2") (pinfunction "2_2") (pintype "passive"))
    )
    (net (code "61") (name "Net-(IC8-VREFAC)") (class "Default")
      (node (ref "C110") (pin "2") (pinfunction "2_2") (pintype "passive"))
      (node (ref "IC8") (pin "2") (pinfunction "VT_2") (pintype "passive"))
      (node (ref "IC8") (pin "3") (pinfunction "VREFAC_3") (pintype "passive"))
    )
    (net (code "62") (name "Net-(IC9-Pad1)") (class "Default")
      (node (ref "IC9") (pin "1") (pinfunction "1_1") (pintype "passive"))
      (node (ref "W10") (pin "1") (pinfunction "1_1") (pintype "passive"))
      (node (ref "W10") (pin "2") (pinfunction "2_2") (pintype "bidirectional"))
    )
    (net (code "63") (name "Net-(IC9-Pad2)") (class "Default")
      (node (ref "IC9") (pin "2") (pinfunction "2_2") (pintype "passive"))
      (node (ref "W10") (pin "3") (pinfunction "3_3") (pintype "bidirectional"))
      (node (ref "W10") (pin "4") (pinfunction "4_4") (pintype "bidirectional"))
    )
    (net (code "64") (name "Net-(Q12-G)") (class "Default")
      (node (ref "Q12") (pin "1") (pinfunction "G_1") (pintype "passive"))
      (node (ref "R68") (pin "2") (pinfunction "2_2") (pintype "passive"))
    )
    (net (code "65") (name "Net-(R65-Pad1)") (class "Default")
      (node (ref "R65") (pin "1") (pinfunction "1_1") (pintype "passive"))
      (node (ref "W6") (pin "1") (pinfunction "1_1") (pintype "bidirectional"))
    )
    (net (code "66") (name "Net-(R66-Pad1)") (class "Default")
      (node (ref "R66") (pin "1") (pinfunction "1_1") (pintype "passive"))
      (node (ref "W7") (pin "1") (pinfunction "1_1") (pintype "bidirectional"))
    )
    (net (code "67") (name "unconnected-(IC7-*IN2-Pad15)") (class "Default")
      (node (ref "IC7") (pin "15") (pinfunction "*IN2_15") (pintype "input+no_connect"))
    )
    (net (code "68") (name "unconnected-(IC7-*INTR-Pad12)") (class "Default")
      (node (ref "IC7") (pin "12") (pinfunction "*INTR_12") (pintype "output+no_connect"))
    )
    (net (code "69") (name "unconnected-(IC7-*OE-Pad11)") (class "Default")
      (node (ref "IC7") (pin "11") (pinfunction "*OE_11") (pintype "input+no_connect"))
    )
    (net (code "70") (name "unconnected-(IC7-*OUT0-Pad23)") (class "Default")
      (node (ref "IC7") (pin "23") (pinfunction "*OUT0_23") (pintype "output+no_connect"))
    )
    (net (code "71") (name "unconnected-(IC7-*OUT3-Pad34)") (class "Default")
      (node (ref "IC7") (pin "34") (pinfunction "*OUT3_34") (pintype "output+no_connect"))
    )
    (net (code "72") (name "unconnected-(IC7-*OUT4-Pad37)") (class "Default")
      (node (ref "IC7") (pin "37") (pinfunction "*OUT4_37") (pintype "output+no_connect"))
    )
    (net (code "73") (name "unconnected-(IC7-*OUT5-Pad41)") (class "Default")
      (node (ref "IC7") (pin "41") (pinfunction "*OUT5_41") (pintype "output+no_connect"))
    )
    (net (code "74") (name "unconnected-(IC7-*OUT6-Pad44)") (class "Default")
      (node (ref "IC7") (pin "44") (pinfunction "*OUT6_44") (pintype "output+no_connect"))
    )
    (net (code "75") (name "unconnected-(IC7-FDEC-Pad25)") (class "Default")
      (node (ref "IC7") (pin "25") (pinfunction "FDEC_25") (pintype "input+no_connect"))
    )
    (net (code "76") (name "unconnected-(IC7-FINC-Pad48)") (class "Default")
      (node (ref "IC7") (pin "48") (pinfunction "FINC_48") (pintype "input+no_connect"))
    )
    (net (code "77") (name "unconnected-(IC7-I2C_SEL-Pad39)") (class "Default")
      (node (ref "IC7") (pin "39") (pinfunction "I2C_SEL_39") (pintype "input+no_connect"))
    )
    (net (code "78") (name "unconnected-(IC7-IN2-Pad14)") (class "Default")
      (node (ref "IC7") (pin "14") (pinfunction "IN2_14") (pintype "input+no_connect"))
    )
    (net (code "79") (name "unconnected-(IC7-OUT0-Pad24)") (class "Default")
      (node (ref "IC7") (pin "24") (pinfunction "OUT0_24") (pintype "output+no_connect"))
    )
    (net (code "80") (name "unconnected-(IC7-OUT3-Pad35)") (class "Default")
      (node (ref "IC7") (pin "35") (pinfunction "OUT3_35") (pintype "output+no_connect"))
    )
    (net (code "81") (name "unconnected-(IC7-OUT4-Pad38)") (class "Default")
      (node (ref "IC7") (pin "38") (pinfunction "OUT4_38") (pintype "output+no_connect"))
    )
    (net (code "82") (name "unconnected-(IC7-OUT5-Pad42)") (class "Default")
      (node (ref "IC7") (pin "42") (pinfunction "OUT5_42") (pintype "output+no_connect"))
    )
    (net (code "83") (name "unconnected-(IC7-OUT6-Pad45)") (class "Default")
      (node (ref "IC7") (pin "45") (pinfunction "OUT6_45") (pintype "output+no_connect"))
    )
    (net (code "84") (name "unconnected-(IC7-RSVD-Pad5)") (class "Default")
      (node (ref "IC7") (pin "5") (pinfunction "RSVD_5") (pintype "passive+no_connect"))
    )
    (net (code "85") (name "unconnected-(IC7-RSVD-Pad20)") (class "Default")
      (node (ref "IC7") (pin "20") (pinfunction "RSVD_20") (pintype "passive+no_connect"))
    )
    (net (code "86") (name "unconnected-(IC7-RSVD-Pad21)") (class "Default")
      (node (ref "IC7") (pin "21") (pinfunction "RSVD_21") (pintype "passive+no_connect"))
    )
    (net (code "87") (name "unconnected-(IC7-RSVD-Pad55)") (class "Default")
      (node (ref "IC7") (pin "55") (pinfunction "RSVD_55") (pintype "passive+no_connect"))
    )
    (net (code "88") (name "unconnected-(IC7-RSVD-Pad56)") (class "Default")
      (node (ref "IC7") (pin "56") (pinfunction "RSVD_56") (pintype "passive+no_connect"))
    )
    (net (code "89") (name "unconnected-(IC7-VDDO0-Pad22)") (class "Default")
      (node (ref "IC7") (pin "22") (pinfunction "VDDO0_22") (pintype "power_in+no_connect"))
    )
    (net (code "90") (name "unconnected-(IC7-VDDO3-Pad33)") (class "Default")
      (node (ref "IC7") (pin "33") (pinfunction "VDDO3_33") (pintype "power_in+no_connect"))
    )
    (net (code "91") (name "unconnected-(IC7-VDDO4-Pad36)") (class "Default")
      (node (ref "IC7") (pin "36") (pinfunction "VDDO4_36") (pintype "power_in+no_connect"))
    )
    (net (code "92") (name "unconnected-(IC7-VDDO5-Pad40)") (class "Default")
      (node (ref "IC7") (pin "40") (pinfunction "VDDO5_40") (pintype "power_in+no_connect"))
    )
    (net (code "93") (name "unconnected-(IC7-VDDO6-Pad43)") (class "Default")
      (node (ref "IC7") (pin "43") (pinfunction "VDDO6_43") (pintype "power_in+no_connect"))
    )
  )
)
